# motherboard_r2.net
KiCad netlist of a schematic drawn in EAGLE
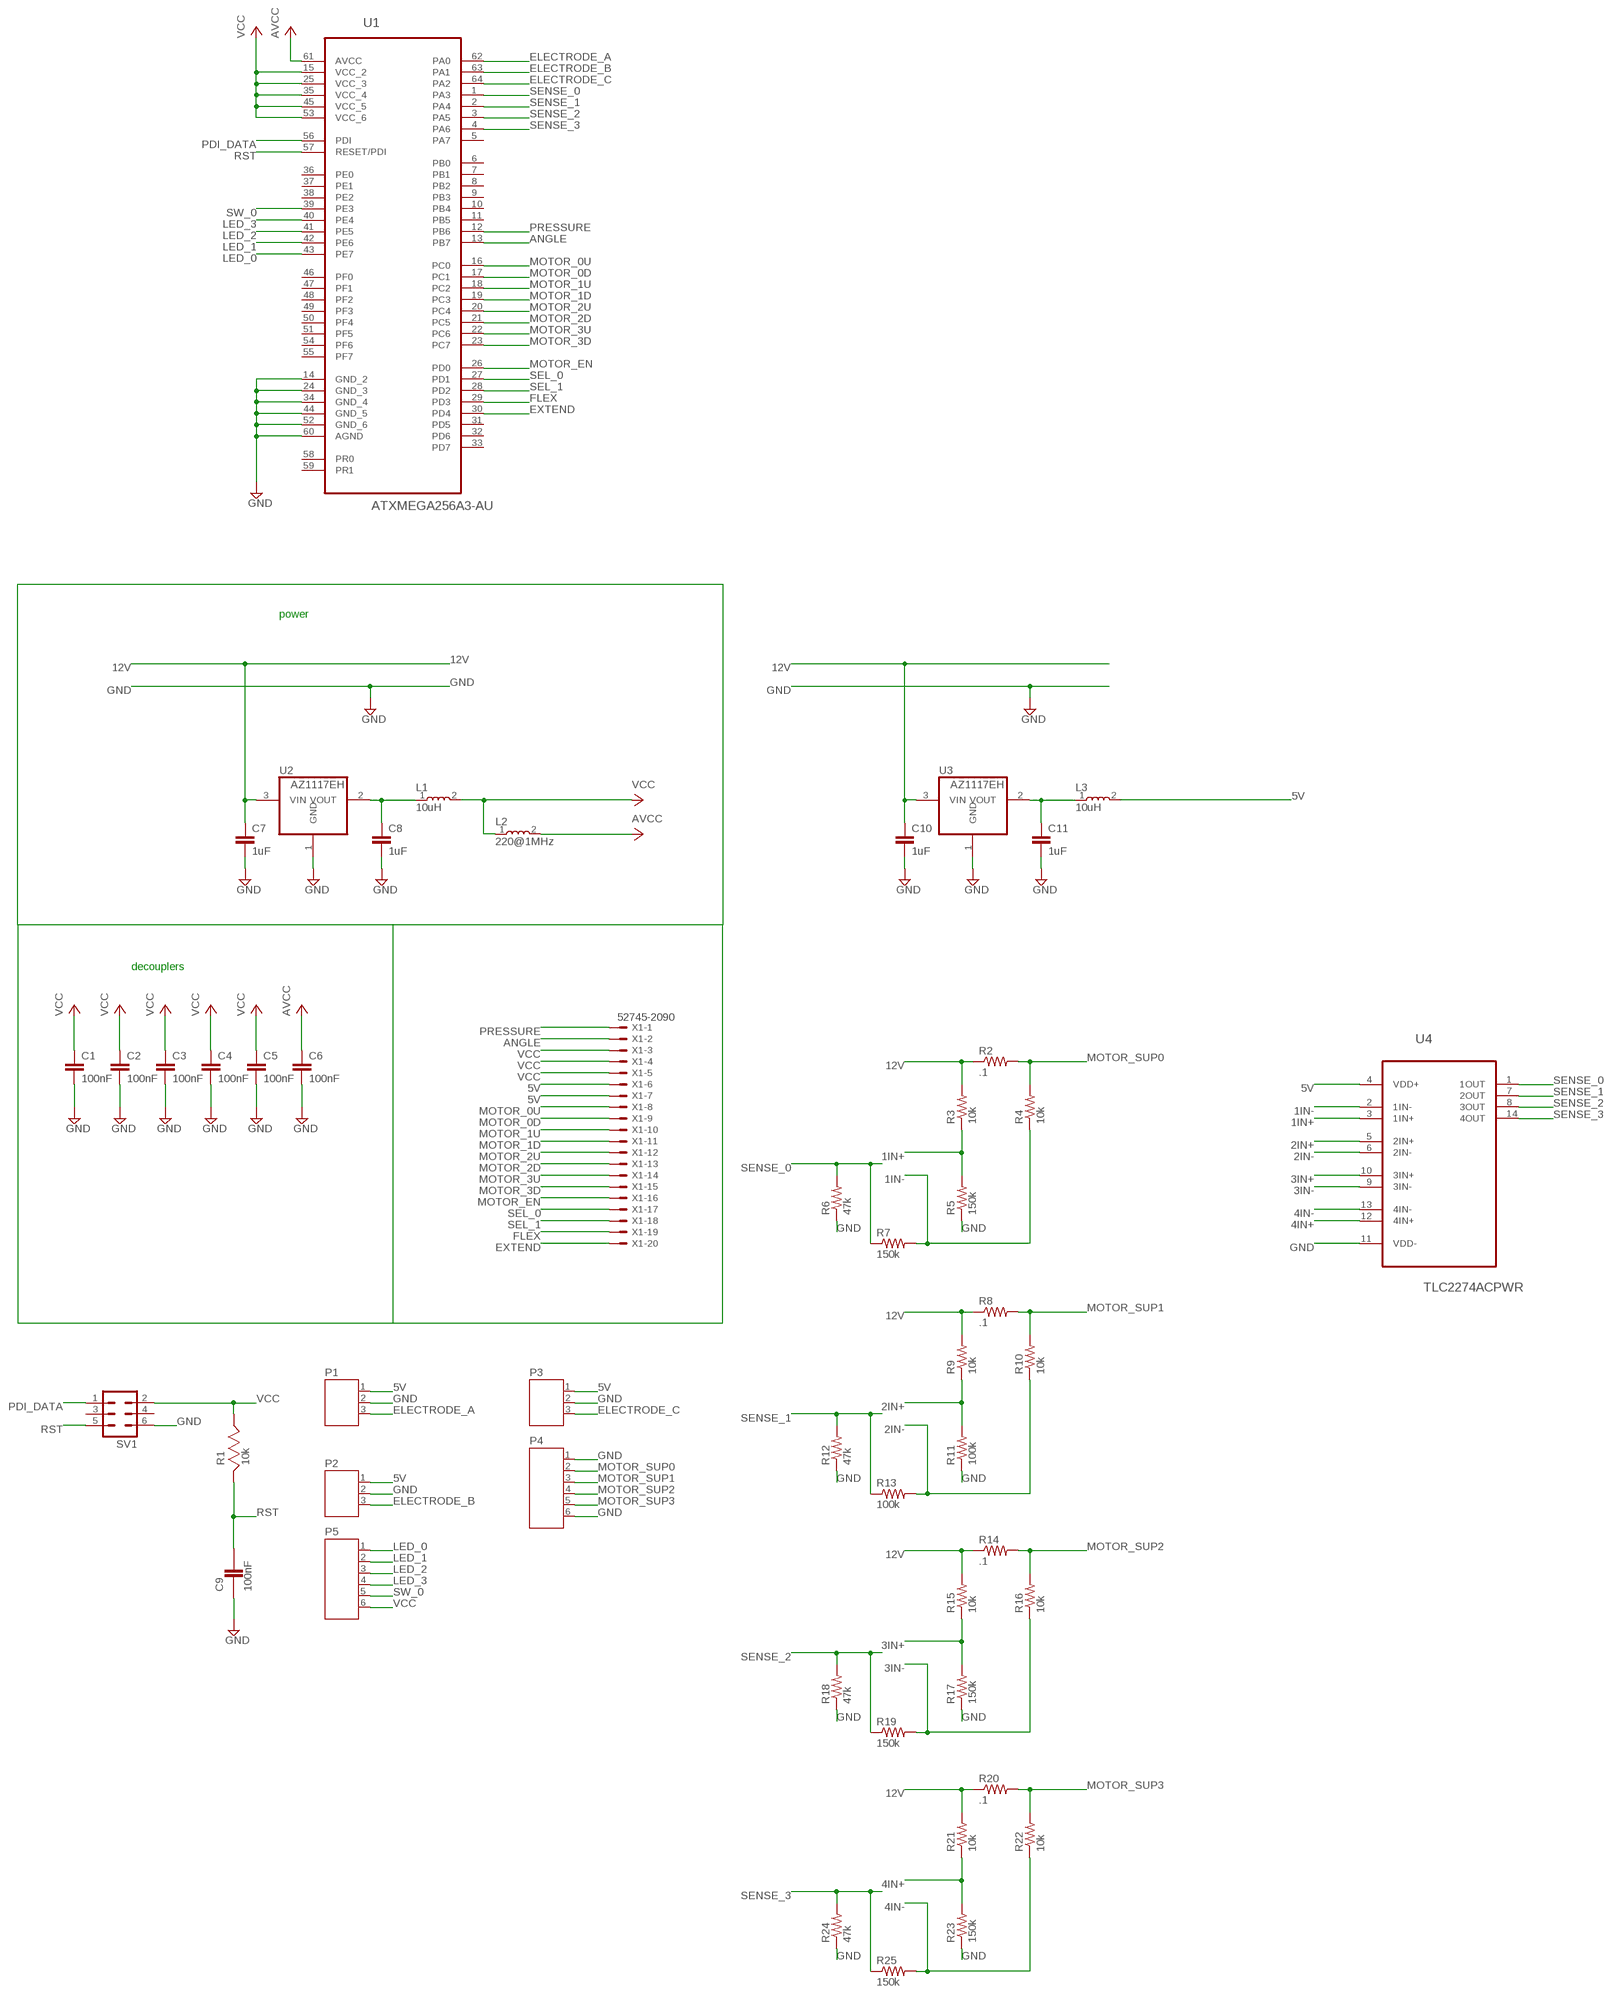
[diagram p0: schematic, sheet 1]

(export (version "E")
  (design (tool "Eeschema 10.0.6"))
  (components
    (comp (ref "C1")
      (value "100nF")
      (footprint "eagle-import:C0603")
      (libsource (lib "eagle-import") (part "C-EUC0603"))
    )
    (comp (ref "C2")
      (value "100nF")
      (footprint "eagle-import:C0603")
      (libsource (lib "eagle-import") (part "C-EUC0603"))
    )
    (comp (ref "C3")
      (value "100nF")
      (footprint "eagle-import:C0603")
      (libsource (lib "eagle-import") (part "C-EUC0603"))
    )
    (comp (ref "C4")
      (value "100nF")
      (footprint "eagle-import:C0603")
      (libsource (lib "eagle-import") (part "C-EUC0603"))
    )
    (comp (ref "C5")
      (value "100nF")
      (footprint "eagle-import:C0603")
      (libsource (lib "eagle-import") (part "C-EUC0603"))
    )
    (comp (ref "C6")
      (value "100nF")
      (footprint "eagle-import:C0603")
      (libsource (lib "eagle-import") (part "C-EUC0603"))
    )
    (comp (ref "C7")
      (value "1uF")
      (footprint "eagle-import:C0603")
      (libsource (lib "eagle-import") (part "C-EUC0603"))
    )
    (comp (ref "C8")
      (value "1uF")
      (footprint "eagle-import:C0603")
      (libsource (lib "eagle-import") (part "C-EUC0603"))
    )
    (comp (ref "C9")
      (value "100nF")
      (footprint "eagle-import:CC0603KRX7R8BB105_CAPC1608X90")
      (fields (field (name "MANUFACTURER") "YAGEO"))
      (libsource (lib "eagle-import") (part "CC0603KRX7R8BB105"))
    )
    (comp (ref "C10")
      (value "1uF")
      (footprint "eagle-import:C0603")
      (libsource (lib "eagle-import") (part "C-EUC0603"))
    )
    (comp (ref "C11")
      (value "1uF")
      (footprint "eagle-import:C0603")
      (libsource (lib "eagle-import") (part "C-EUC0603"))
    )
    (comp (ref "L1")
      (value "10uH")
      (footprint "eagle-import:0805")
      (libsource (lib "eagle-import") (part "L0805"))
    )
    (comp (ref "L2")
      (value "220@1MHz")
      (footprint "eagle-import:0805")
      (libsource (lib "eagle-import") (part "L0805"))
    )
    (comp (ref "L3")
      (value "10uH")
      (footprint "eagle-import:0805")
      (libsource (lib "eagle-import") (part "L0805"))
    )
    (comp (ref "P1")
      (value "JST-PH3")
      (footprint "eagle-import:JST-PH3")
      (libsource (lib "eagle-import") (part "JST-PH3"))
    )
    (comp (ref "P2")
      (value "JST-PH3")
      (footprint "eagle-import:JST-PH3")
      (libsource (lib "eagle-import") (part "JST-PH3"))
    )
    (comp (ref "P3")
      (value "JST-PH3")
      (footprint "eagle-import:JST-PH3")
      (libsource (lib "eagle-import") (part "JST-PH3"))
    )
    (comp (ref "P4")
      (value "JST-PH6")
      (footprint "eagle-import:JST-PH6")
      (libsource (lib "eagle-import") (part "JST-PH6"))
    )
    (comp (ref "P5")
      (value "JST-PH6")
      (footprint "eagle-import:JST-PH6")
      (libsource (lib "eagle-import") (part "JST-PH6"))
    )
    (comp (ref "R1")
      (value "10k")
      (footprint "eagle-import:CRCW060310K0FKEA_RESC1608X55")
      (fields (field (name "MANUFACTURER") "VISHAY"))
      (libsource (lib "eagle-import") (part "CRCW060310K0FKEA"))
    )
    (comp (ref "R2")
      (value ".1")
      (footprint "eagle-import:R0603")
      (libsource (lib "eagle-import") (part "R-US_R0603"))
    )
    (comp (ref "R3")
      (value "10k")
      (footprint "eagle-import:R0603")
      (libsource (lib "eagle-import") (part "R-US_R0603"))
    )
    (comp (ref "R4")
      (value "10k")
      (footprint "eagle-import:R0603")
      (libsource (lib "eagle-import") (part "R-US_R0603"))
    )
    (comp (ref "R5")
      (value "150k")
      (footprint "eagle-import:R0603")
      (libsource (lib "eagle-import") (part "R-US_R0603"))
    )
    (comp (ref "R6")
      (value "47k")
      (footprint "eagle-import:R0603")
      (libsource (lib "eagle-import") (part "R-US_R0603"))
    )
    (comp (ref "R7")
      (value "150k")
      (footprint "eagle-import:R0603")
      (libsource (lib "eagle-import") (part "R-US_R0603"))
    )
    (comp (ref "R8")
      (value ".1")
      (footprint "eagle-import:R0603")
      (libsource (lib "eagle-import") (part "R-US_R0603"))
    )
    (comp (ref "R9")
      (value "10k")
      (footprint "eagle-import:R0603")
      (libsource (lib "eagle-import") (part "R-US_R0603"))
    )
    (comp (ref "R10")
      (value "10k")
      (footprint "eagle-import:R0603")
      (libsource (lib "eagle-import") (part "R-US_R0603"))
    )
    (comp (ref "R11")
      (value "100k")
      (footprint "eagle-import:R0603")
      (libsource (lib "eagle-import") (part "R-US_R0603"))
    )
    (comp (ref "R12")
      (value "47k")
      (footprint "eagle-import:R0603")
      (libsource (lib "eagle-import") (part "R-US_R0603"))
    )
    (comp (ref "R13")
      (value "100k")
      (footprint "eagle-import:R0603")
      (libsource (lib "eagle-import") (part "R-US_R0603"))
    )
    (comp (ref "R14")
      (value ".1")
      (footprint "eagle-import:R0603")
      (libsource (lib "eagle-import") (part "R-US_R0603"))
    )
    (comp (ref "R15")
      (value "10k")
      (footprint "eagle-import:R0603")
      (libsource (lib "eagle-import") (part "R-US_R0603"))
    )
    (comp (ref "R16")
      (value "10k")
      (footprint "eagle-import:R0603")
      (libsource (lib "eagle-import") (part "R-US_R0603"))
    )
    (comp (ref "R17")
      (value "150k")
      (footprint "eagle-import:R0603")
      (libsource (lib "eagle-import") (part "R-US_R0603"))
    )
    (comp (ref "R18")
      (value "47k")
      (footprint "eagle-import:R0603")
      (libsource (lib "eagle-import") (part "R-US_R0603"))
    )
    (comp (ref "R19")
      (value "150k")
      (footprint "eagle-import:R0603")
      (libsource (lib "eagle-import") (part "R-US_R0603"))
    )
    (comp (ref "R20")
      (value ".1")
      (footprint "eagle-import:R0603")
      (libsource (lib "eagle-import") (part "R-US_R0603"))
    )
    (comp (ref "R21")
      (value "10k")
      (footprint "eagle-import:R0603")
      (libsource (lib "eagle-import") (part "R-US_R0603"))
    )
    (comp (ref "R22")
      (value "10k")
      (footprint "eagle-import:R0603")
      (libsource (lib "eagle-import") (part "R-US_R0603"))
    )
    (comp (ref "R23")
      (value "150k")
      (footprint "eagle-import:R0603")
      (libsource (lib "eagle-import") (part "R-US_R0603"))
    )
    (comp (ref "R24")
      (value "47k")
      (footprint "eagle-import:R0603")
      (libsource (lib "eagle-import") (part "R-US_R0603"))
    )
    (comp (ref "R25")
      (value "150k")
      (footprint "eagle-import:R0603")
      (libsource (lib "eagle-import") (part "R-US_R0603"))
    )
    (comp (ref "SV1")
      (value "MA03-2")
      (footprint "eagle-import:MA03-2")
      (libsource (lib "eagle-import") (part "MA03-2"))
    )
    (comp (ref "U1")
      (value "ATXMEGA256A3-AU")
      (footprint "eagle-import:QFP80P1600X1600X120-64N")
      (fields (field (name "MF") "Atmel"))
      (libsource (lib "eagle-import") (part "ATXMEGA256A3-AU"))
    )
    (comp (ref "U2")
      (value "AZ1117EH")
      (footprint "eagle-import:SOT230P700X160-4N")
      (libsource (lib "eagle-import") (part "AZ1117EH"))
    )
    (comp (ref "U3")
      (value "AZ1117EH")
      (footprint "eagle-import:SOT230P700X160-4N")
      (libsource (lib "eagle-import") (part "AZ1117EH"))
    )
    (comp (ref "U4")
      (value "TLC2274ACPWR")
      (footprint "eagle-import:SOP65P640X120-14N")
      (fields (field (name "MF") "Texas Instruments"))
      (libsource (lib "eagle-import") (part "TLC2274ACPWR"))
    )
    (comp (ref "X1")
      (value "52745-2090")
      (footprint "eagle-import:52745-2090")
      (fields (field (name "MF") "WALDOM/MOLEX"))
      (libsource (lib "eagle-import") (part "52745-2090"))
    )
  )
  (nets
    (net (code "1") (name "/1IN+") (class "Default")
      (node (ref "R3") (pin "1") (pinfunction "1_1") (pintype "passive"))
      (node (ref "R5") (pin "2") (pinfunction "2_2") (pintype "passive"))
      (node (ref "U4") (pin "3") (pinfunction "1IN+_3") (pintype "input"))
    )
    (net (code "2") (name "/1IN-") (class "Default")
      (node (ref "R4") (pin "1") (pinfunction "1_1") (pintype "passive"))
      (node (ref "R7") (pin "2") (pinfunction "2_2") (pintype "passive"))
      (node (ref "U4") (pin "2") (pinfunction "1IN-_2") (pintype "input"))
    )
    (net (code "3") (name "/2IN+") (class "Default")
      (node (ref "R11") (pin "2") (pinfunction "2_2") (pintype "passive"))
      (node (ref "R9") (pin "1") (pinfunction "1_1") (pintype "passive"))
      (node (ref "U4") (pin "5") (pinfunction "2IN+_5") (pintype "input"))
    )
    (net (code "4") (name "/2IN-") (class "Default")
      (node (ref "R10") (pin "1") (pinfunction "1_1") (pintype "passive"))
      (node (ref "R13") (pin "2") (pinfunction "2_2") (pintype "passive"))
      (node (ref "U4") (pin "6") (pinfunction "2IN-_6") (pintype "input"))
    )
    (net (code "5") (name "/3IN+") (class "Default")
      (node (ref "R15") (pin "1") (pinfunction "1_1") (pintype "passive"))
      (node (ref "R17") (pin "2") (pinfunction "2_2") (pintype "passive"))
      (node (ref "U4") (pin "10") (pinfunction "3IN+_10") (pintype "input"))
    )
    (net (code "6") (name "/3IN-") (class "Default")
      (node (ref "R16") (pin "1") (pinfunction "1_1") (pintype "passive"))
      (node (ref "R19") (pin "2") (pinfunction "2_2") (pintype "passive"))
      (node (ref "U4") (pin "9") (pinfunction "3IN-_9") (pintype "input"))
    )
    (net (code "7") (name "/4IN+") (class "Default")
      (node (ref "R21") (pin "1") (pinfunction "1_1") (pintype "passive"))
      (node (ref "R23") (pin "2") (pinfunction "2_2") (pintype "passive"))
      (node (ref "U4") (pin "12") (pinfunction "4IN+_12") (pintype "input"))
    )
    (net (code "8") (name "/4IN-") (class "Default")
      (node (ref "R22") (pin "1") (pinfunction "1_1") (pintype "passive"))
      (node (ref "R25") (pin "2") (pinfunction "2_2") (pintype "passive"))
      (node (ref "U4") (pin "13") (pinfunction "4IN-_13") (pintype "input"))
    )
    (net (code "9") (name "/5V") (class "Default")
      (node (ref "L3") (pin "2") (pinfunction "2_2") (pintype "passive"))
      (node (ref "P1") (pin "1") (pinfunction "1_1") (pintype "passive"))
      (node (ref "P2") (pin "1") (pinfunction "1_1") (pintype "passive"))
      (node (ref "P3") (pin "1") (pinfunction "1_1") (pintype "passive"))
      (node (ref "U4") (pin "4") (pinfunction "VDD+_4") (pintype "power_in"))
      (node (ref "X1") (pin "6") (pinfunction "S_6") (pintype "passive"))
      (node (ref "X1") (pin "7") (pinfunction "S_7") (pintype "passive"))
    )
    (net (code "10") (name "/12V") (class "Default")
      (node (ref "C10") (pin "1") (pinfunction "1_1") (pintype "passive"))
      (node (ref "C7") (pin "1") (pinfunction "1_1") (pintype "passive"))
      (node (ref "R14") (pin "1") (pinfunction "1_1") (pintype "passive"))
      (node (ref "R15") (pin "2") (pinfunction "2_2") (pintype "passive"))
      (node (ref "R2") (pin "1") (pinfunction "1_1") (pintype "passive"))
      (node (ref "R20") (pin "1") (pinfunction "1_1") (pintype "passive"))
      (node (ref "R21") (pin "2") (pinfunction "2_2") (pintype "passive"))
      (node (ref "R3") (pin "2") (pinfunction "2_2") (pintype "passive"))
      (node (ref "R8") (pin "1") (pinfunction "1_1") (pintype "passive"))
      (node (ref "R9") (pin "2") (pinfunction "2_2") (pintype "passive"))
      (node (ref "U2") (pin "3") (pinfunction "VIN_3") (pintype "input"))
      (node (ref "U3") (pin "3") (pinfunction "VIN_3") (pintype "input"))
    )
    (net (code "11") (name "/ANGLE") (class "Default")
      (node (ref "U1") (pin "13") (pinfunction "PB7_13") (pintype "bidirectional"))
      (node (ref "X1") (pin "2") (pinfunction "S_2") (pintype "passive"))
    )
    (net (code "12") (name "/ELECTRODE_A") (class "Default")
      (node (ref "P1") (pin "3") (pinfunction "3_3") (pintype "passive"))
      (node (ref "U1") (pin "62") (pinfunction "PA0_62") (pintype "bidirectional"))
    )
    (net (code "13") (name "/ELECTRODE_B") (class "Default")
      (node (ref "P2") (pin "3") (pinfunction "3_3") (pintype "passive"))
      (node (ref "U1") (pin "63") (pinfunction "PA1_63") (pintype "bidirectional"))
    )
    (net (code "14") (name "/ELECTRODE_C") (class "Default")
      (node (ref "P3") (pin "3") (pinfunction "3_3") (pintype "passive"))
      (node (ref "U1") (pin "64") (pinfunction "PA2_64") (pintype "bidirectional"))
    )
    (net (code "15") (name "/EXTEND") (class "Default")
      (node (ref "U1") (pin "30") (pinfunction "PD4_30") (pintype "bidirectional"))
      (node (ref "X1") (pin "20") (pinfunction "S_20") (pintype "passive"))
    )
    (net (code "16") (name "/FLEX") (class "Default")
      (node (ref "U1") (pin "29") (pinfunction "PD3_29") (pintype "bidirectional"))
      (node (ref "X1") (pin "19") (pinfunction "S_19") (pintype "passive"))
    )
    (net (code "17") (name "/LED_0") (class "Default")
      (node (ref "P5") (pin "1") (pinfunction "1_1") (pintype "passive"))
      (node (ref "U1") (pin "43") (pinfunction "PE7_43") (pintype "bidirectional"))
    )
    (net (code "18") (name "/LED_1") (class "Default")
      (node (ref "P5") (pin "2") (pinfunction "2_2") (pintype "passive"))
      (node (ref "U1") (pin "42") (pinfunction "PE6_42") (pintype "bidirectional"))
    )
    (net (code "19") (name "/LED_2") (class "Default")
      (node (ref "P5") (pin "3") (pinfunction "3_3") (pintype "passive"))
      (node (ref "U1") (pin "41") (pinfunction "PE5_41") (pintype "bidirectional"))
    )
    (net (code "20") (name "/LED_3") (class "Default")
      (node (ref "P5") (pin "4") (pinfunction "4_4") (pintype "passive"))
      (node (ref "U1") (pin "40") (pinfunction "PE4_40") (pintype "bidirectional"))
    )
    (net (code "21") (name "/MOTOR_0D") (class "Default")
      (node (ref "U1") (pin "17") (pinfunction "PC1_17") (pintype "bidirectional"))
      (node (ref "X1") (pin "9") (pinfunction "S_9") (pintype "passive"))
    )
    (net (code "22") (name "/MOTOR_0U") (class "Default")
      (node (ref "U1") (pin "16") (pinfunction "PC0_16") (pintype "bidirectional"))
      (node (ref "X1") (pin "8") (pinfunction "S_8") (pintype "passive"))
    )
    (net (code "23") (name "/MOTOR_1D") (class "Default")
      (node (ref "U1") (pin "19") (pinfunction "PC3_19") (pintype "bidirectional"))
      (node (ref "X1") (pin "11") (pinfunction "S_11") (pintype "passive"))
    )
    (net (code "24") (name "/MOTOR_1U") (class "Default")
      (node (ref "U1") (pin "18") (pinfunction "PC2_18") (pintype "bidirectional"))
      (node (ref "X1") (pin "10") (pinfunction "S_10") (pintype "passive"))
    )
    (net (code "25") (name "/MOTOR_2D") (class "Default")
      (node (ref "U1") (pin "21") (pinfunction "PC5_21") (pintype "bidirectional"))
      (node (ref "X1") (pin "13") (pinfunction "S_13") (pintype "passive"))
    )
    (net (code "26") (name "/MOTOR_2U") (class "Default")
      (node (ref "U1") (pin "20") (pinfunction "PC4_20") (pintype "bidirectional"))
      (node (ref "X1") (pin "12") (pinfunction "S_12") (pintype "passive"))
    )
    (net (code "27") (name "/MOTOR_3D") (class "Default")
      (node (ref "U1") (pin "23") (pinfunction "PC7_23") (pintype "bidirectional"))
      (node (ref "X1") (pin "15") (pinfunction "S_15") (pintype "passive"))
    )
    (net (code "28") (name "/MOTOR_3U") (class "Default")
      (node (ref "U1") (pin "22") (pinfunction "PC6_22") (pintype "bidirectional"))
      (node (ref "X1") (pin "14") (pinfunction "S_14") (pintype "passive"))
    )
    (net (code "29") (name "/MOTOR_EN") (class "Default")
      (node (ref "U1") (pin "26") (pinfunction "PD0_26") (pintype "bidirectional"))
      (node (ref "X1") (pin "16") (pinfunction "S_16") (pintype "passive"))
    )
    (net (code "30") (name "/MOTOR_SUP0") (class "Default")
      (node (ref "P4") (pin "2") (pinfunction "2_2") (pintype "passive"))
      (node (ref "R2") (pin "2") (pinfunction "2_2") (pintype "passive"))
      (node (ref "R4") (pin "2") (pinfunction "2_2") (pintype "passive"))
    )
    (net (code "31") (name "/MOTOR_SUP1") (class "Default")
      (node (ref "P4") (pin "3") (pinfunction "3_3") (pintype "passive"))
      (node (ref "R10") (pin "2") (pinfunction "2_2") (pintype "passive"))
      (node (ref "R8") (pin "2") (pinfunction "2_2") (pintype "passive"))
    )
    (net (code "32") (name "/MOTOR_SUP2") (class "Default")
      (node (ref "P4") (pin "4") (pinfunction "4_4") (pintype "passive"))
      (node (ref "R14") (pin "2") (pinfunction "2_2") (pintype "passive"))
      (node (ref "R16") (pin "2") (pinfunction "2_2") (pintype "passive"))
    )
    (net (code "33") (name "/MOTOR_SUP3") (class "Default")
      (node (ref "P4") (pin "5") (pinfunction "5_5") (pintype "passive"))
      (node (ref "R20") (pin "2") (pinfunction "2_2") (pintype "passive"))
      (node (ref "R22") (pin "2") (pinfunction "2_2") (pintype "passive"))
    )
    (net (code "34") (name "/PDI_DATA") (class "Default")
      (node (ref "SV1") (pin "1") (pinfunction "1_1") (pintype "passive"))
      (node (ref "U1") (pin "56") (pinfunction "PDI_56") (pintype "input"))
    )
    (net (code "35") (name "/PRESSURE") (class "Default")
      (node (ref "U1") (pin "12") (pinfunction "PB6_12") (pintype "bidirectional"))
      (node (ref "X1") (pin "1") (pinfunction "S_1") (pintype "passive"))
    )
    (net (code "36") (name "/RST") (class "Default")
      (node (ref "C9") (pin "2") (pinfunction "2_2") (pintype "passive"))
      (node (ref "R1") (pin "1") (pinfunction "1_1") (pintype "passive"))
      (node (ref "SV1") (pin "5") (pinfunction "5_5") (pintype "passive"))
      (node (ref "U1") (pin "57") (pinfunction "RESET/PDI_57") (pintype "input"))
    )
    (net (code "37") (name "/SEL_0") (class "Default")
      (node (ref "U1") (pin "27") (pinfunction "PD1_27") (pintype "bidirectional"))
      (node (ref "X1") (pin "17") (pinfunction "S_17") (pintype "passive"))
    )
    (net (code "38") (name "/SEL_1") (class "Default")
      (node (ref "U1") (pin "28") (pinfunction "PD2_28") (pintype "bidirectional"))
      (node (ref "X1") (pin "18") (pinfunction "S_18") (pintype "passive"))
    )
    (net (code "39") (name "/SENSE_0") (class "Default")
      (node (ref "R6") (pin "2") (pinfunction "2_2") (pintype "passive"))
      (node (ref "R7") (pin "1") (pinfunction "1_1") (pintype "passive"))
      (node (ref "U1") (pin "1") (pinfunction "PA3_1") (pintype "bidirectional"))
      (node (ref "U4") (pin "1") (pinfunction "1OUT_1") (pintype "output"))
    )
    (net (code "40") (name "/SENSE_1") (class "Default")
      (node (ref "R12") (pin "2") (pinfunction "2_2") (pintype "passive"))
      (node (ref "R13") (pin "1") (pinfunction "1_1") (pintype "passive"))
      (node (ref "U1") (pin "2") (pinfunction "PA4_2") (pintype "bidirectional"))
      (node (ref "U4") (pin "7") (pinfunction "2OUT_7") (pintype "output"))
    )
    (net (code "41") (name "/SENSE_2") (class "Default")
      (node (ref "R18") (pin "2") (pinfunction "2_2") (pintype "passive"))
      (node (ref "R19") (pin "1") (pinfunction "1_1") (pintype "passive"))
      (node (ref "U1") (pin "3") (pinfunction "PA5_3") (pintype "bidirectional"))
      (node (ref "U4") (pin "8") (pinfunction "3OUT_8") (pintype "output"))
    )
    (net (code "42") (name "/SENSE_3") (class "Default")
      (node (ref "R24") (pin "2") (pinfunction "2_2") (pintype "passive"))
      (node (ref "R25") (pin "1") (pinfunction "1_1") (pintype "passive"))
      (node (ref "U1") (pin "4") (pinfunction "PA6_4") (pintype "bidirectional"))
      (node (ref "U4") (pin "14") (pinfunction "4OUT_14") (pintype "output"))
    )
    (net (code "43") (name "/SW_0") (class "Default")
      (node (ref "P5") (pin "5") (pinfunction "5_5") (pintype "passive"))
      (node (ref "U1") (pin "39") (pinfunction "PE3_39") (pintype "bidirectional"))
    )
    (net (code "44") (name "AVCC") (class "Default")
      (node (ref "C6") (pin "1") (pinfunction "1_1") (pintype "passive"))
      (node (ref "L2") (pin "2") (pinfunction "2_2") (pintype "passive"))
      (node (ref "U1") (pin "61") (pinfunction "AVCC_61") (pintype "power_in"))
    )
    (net (code "45") (name "GND") (class "Default")
      (node (ref "C1") (pin "2") (pinfunction "2_2") (pintype "passive"))
      (node (ref "C10") (pin "2") (pinfunction "2_2") (pintype "passive"))
      (node (ref "C11") (pin "2") (pinfunction "2_2") (pintype "passive"))
      (node (ref "C2") (pin "2") (pinfunction "2_2") (pintype "passive"))
      (node (ref "C3") (pin "2") (pinfunction "2_2") (pintype "passive"))
      (node (ref "C4") (pin "2") (pinfunction "2_2") (pintype "passive"))
      (node (ref "C5") (pin "2") (pinfunction "2_2") (pintype "passive"))
      (node (ref "C6") (pin "2") (pinfunction "2_2") (pintype "passive"))
      (node (ref "C7") (pin "2") (pinfunction "2_2") (pintype "passive"))
      (node (ref "C8") (pin "2") (pinfunction "2_2") (pintype "passive"))
      (node (ref "C9") (pin "1") (pinfunction "1_1") (pintype "passive"))
      (node (ref "P1") (pin "2") (pinfunction "2_2") (pintype "passive"))
      (node (ref "P2") (pin "2") (pinfunction "2_2") (pintype "passive"))
      (node (ref "P3") (pin "2") (pinfunction "2_2") (pintype "passive"))
      (node (ref "P4") (pin "1") (pinfunction "1_1") (pintype "passive"))
      (node (ref "P4") (pin "6") (pinfunction "6_6") (pintype "passive"))
      (node (ref "R11") (pin "1") (pinfunction "1_1") (pintype "passive"))
      (node (ref "R12") (pin "1") (pinfunction "1_1") (pintype "passive"))
      (node (ref "R17") (pin "1") (pinfunction "1_1") (pintype "passive"))
      (node (ref "R18") (pin "1") (pinfunction "1_1") (pintype "passive"))
      (node (ref "R23") (pin "1") (pinfunction "1_1") (pintype "passive"))
      (node (ref "R24") (pin "1") (pinfunction "1_1") (pintype "passive"))
      (node (ref "R5") (pin "1") (pinfunction "1_1") (pintype "passive"))
      (node (ref "R6") (pin "1") (pinfunction "1_1") (pintype "passive"))
      (node (ref "SV1") (pin "6") (pinfunction "6_6") (pintype "passive"))
      (node (ref "U1") (pin "14") (pinfunction "GND_2_14") (pintype "passive"))
      (node (ref "U1") (pin "24") (pinfunction "GND_3_24") (pintype "passive"))
      (node (ref "U1") (pin "34") (pinfunction "GND_4_34") (pintype "passive"))
      (node (ref "U1") (pin "44") (pinfunction "GND_5_44") (pintype "passive"))
      (node (ref "U1") (pin "52") (pinfunction "GND_6_52") (pintype "passive"))
      (node (ref "U1") (pin "60") (pinfunction "AGND_60") (pintype "passive"))
      (node (ref "U2") (pin "1") (pinfunction "GND_1") (pintype "power_in"))
      (node (ref "U3") (pin "1") (pinfunction "GND_1") (pintype "power_in"))
      (node (ref "U4") (pin "11") (pinfunction "VDD-_11") (pintype "power_in"))
    )
    (net (code "46") (name "Net-(U2-VOUT)") (class "Default")
      (node (ref "C8") (pin "1") (pinfunction "1_1") (pintype "passive"))
      (node (ref "L1") (pin "1") (pinfunction "1_1") (pintype "passive"))
      (node (ref "U2") (pin "2") (pinfunction "VOUT_2") (pintype "output"))
    )
    (net (code "47") (name "Net-(U3-VOUT)") (class "Default")
      (node (ref "C11") (pin "1") (pinfunction "1_1") (pintype "passive"))
      (node (ref "L3") (pin "1") (pinfunction "1_1") (pintype "passive"))
      (node (ref "U3") (pin "2") (pinfunction "VOUT_2") (pintype "output"))
    )
    (net (code "48") (name "VCC") (class "Default")
      (node (ref "C1") (pin "1") (pinfunction "1_1") (pintype "passive"))
      (node (ref "C2") (pin "1") (pinfunction "1_1") (pintype "passive"))
      (node (ref "C3") (pin "1") (pinfunction "1_1") (pintype "passive"))
      (node (ref "C4") (pin "1") (pinfunction "1_1") (pintype "passive"))
      (node (ref "C5") (pin "1") (pinfunction "1_1") (pintype "passive"))
      (node (ref "L1") (pin "2") (pinfunction "2_2") (pintype "passive"))
      (node (ref "L2") (pin "1") (pinfunction "1_1") (pintype "passive"))
      (node (ref "P5") (pin "6") (pinfunction "6_6") (pintype "passive"))
      (node (ref "R1") (pin "2") (pinfunction "2_2") (pintype "passive"))
      (node (ref "SV1") (pin "2") (pinfunction "2_2") (pintype "passive"))
      (node (ref "U1") (pin "15") (pinfunction "VCC_2_15") (pintype "power_in"))
      (node (ref "U1") (pin "25") (pinfunction "VCC_3_25") (pintype "power_in"))
      (node (ref "U1") (pin "35") (pinfunction "VCC_4_35") (pintype "power_in"))
      (node (ref "U1") (pin "45") (pinfunction "VCC_5_45") (pintype "power_in"))
      (node (ref "U1") (pin "53") (pinfunction "VCC_6_53") (pintype "power_in"))
      (node (ref "X1") (pin "3") (pinfunction "S_3") (pintype "passive"))
      (node (ref "X1") (pin "4") (pinfunction "S_4") (pintype "passive"))
      (node (ref "X1") (pin "5") (pinfunction "S_5") (pintype "passive"))
    )
    (net (code "49") (name "unconnected-(SV1-Pad3)") (class "Default")
      (node (ref "SV1") (pin "3") (pinfunction "3_3") (pintype "passive"))
    )
    (net (code "50") (name "unconnected-(SV1-Pad4)") (class "Default")
      (node (ref "SV1") (pin "4") (pinfunction "4_4") (pintype "passive"))
    )
    (net (code "51") (name "unconnected-(U1-PA7-Pad5)") (class "Default")
      (node (ref "U1") (pin "5") (pinfunction "PA7_5") (pintype "bidirectional"))
    )
    (net (code "52") (name "unconnected-(U1-PB0-Pad6)") (class "Default")
      (node (ref "U1") (pin "6") (pinfunction "PB0_6") (pintype "bidirectional"))
    )
    (net (code "53") (name "unconnected-(U1-PB1-Pad7)") (class "Default")
      (node (ref "U1") (pin "7") (pinfunction "PB1_7") (pintype "bidirectional"))
    )
    (net (code "54") (name "unconnected-(U1-PB2-Pad8)") (class "Default")
      (node (ref "U1") (pin "8") (pinfunction "PB2_8") (pintype "bidirectional"))
    )
    (net (code "55") (name "unconnected-(U1-PB3-Pad9)") (class "Default")
      (node (ref "U1") (pin "9") (pinfunction "PB3_9") (pintype "bidirectional"))
    )
    (net (code "56") (name "unconnected-(U1-PB4-Pad10)") (class "Default")
      (node (ref "U1") (pin "10") (pinfunction "PB4_10") (pintype "bidirectional"))
    )
    (net (code "57") (name "unconnected-(U1-PB5-Pad11)") (class "Default")
      (node (ref "U1") (pin "11") (pinfunction "PB5_11") (pintype "bidirectional"))
    )
    (net (code "58") (name "unconnected-(U1-PD5-Pad31)") (class "Default")
      (node (ref "U1") (pin "31") (pinfunction "PD5_31") (pintype "bidirectional"))
    )
    (net (code "59") (name "unconnected-(U1-PD6-Pad32)") (class "Default")
      (node (ref "U1") (pin "32") (pinfunction "PD6_32") (pintype "bidirectional"))
    )
    (net (code "60") (name "unconnected-(U1-PD7-Pad33)") (class "Default")
      (node (ref "U1") (pin "33") (pinfunction "PD7_33") (pintype "bidirectional"))
    )
    (net (code "61") (name "unconnected-(U1-PE0-Pad36)") (class "Default")
      (node (ref "U1") (pin "36") (pinfunction "PE0_36") (pintype "bidirectional"))
    )
    (net (code "62") (name "unconnected-(U1-PE1-Pad37)") (class "Default")
      (node (ref "U1") (pin "37") (pinfunction "PE1_37") (pintype "bidirectional"))
    )
    (net (code "63") (name "unconnected-(U1-PE2-Pad38)") (class "Default")
      (node (ref "U1") (pin "38") (pinfunction "PE2_38") (pintype "bidirectional"))
    )
    (net (code "64") (name "unconnected-(U1-PF0-Pad46)") (class "Default")
      (node (ref "U1") (pin "46") (pinfunction "PF0_46") (pintype "bidirectional"))
    )
    (net (code "65") (name "unconnected-(U1-PF1-Pad47)") (class "Default")
      (node (ref "U1") (pin "47") (pinfunction "PF1_47") (pintype "bidirectional"))
    )
    (net (code "66") (name "unconnected-(U1-PF2-Pad48)") (class "Default")
      (node (ref "U1") (pin "48") (pinfunction "PF2_48") (pintype "bidirectional"))
    )
    (net (code "67") (name "unconnected-(U1-PF3-Pad49)") (class "Default")
      (node (ref "U1") (pin "49") (pinfunction "PF3_49") (pintype "bidirectional"))
    )
    (net (code "68") (name "unconnected-(U1-PF4-Pad50)") (class "Default")
      (node (ref "U1") (pin "50") (pinfunction "PF4_50") (pintype "bidirectional"))
    )
    (net (code "69") (name "unconnected-(U1-PF5-Pad51)") (class "Default")
      (node (ref "U1") (pin "51") (pinfunction "PF5_51") (pintype "bidirectional"))
    )
    (net (code "70") (name "unconnected-(U1-PF6-Pad54)") (class "Default")
      (node (ref "U1") (pin "54") (pinfunction "PF6_54") (pintype "bidirectional"))
    )
    (net (code "71") (name "unconnected-(U1-PF7-Pad55)") (class "Default")
      (node (ref "U1") (pin "55") (pinfunction "PF7_55") (pintype "bidirectional"))
    )
    (net (code "72") (name "unconnected-(U1-PR0-Pad58)") (class "Default")
      (node (ref "U1") (pin "58") (pinfunction "PR0_58") (pintype "input"))
    )
    (net (code "73") (name "unconnected-(U1-PR1-Pad59)") (class "Default")
      (node (ref "U1") (pin "59") (pinfunction "PR1_59") (pintype "input"))
    )
  )
)
